# 3V3Regulator.net
KiCad netlist of a schematic drawn in Altium Designer
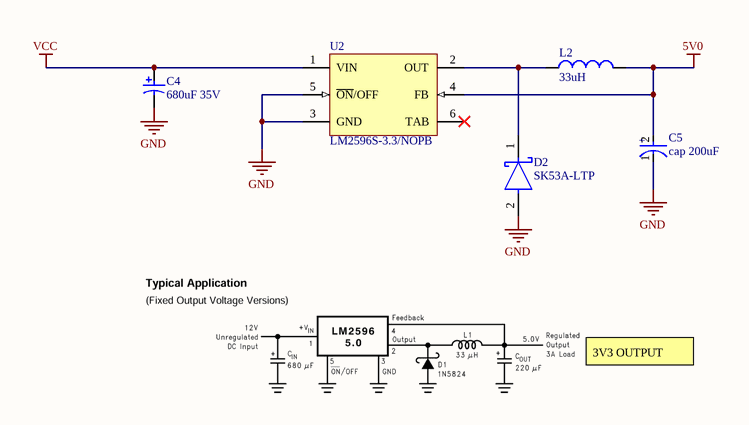
[diagram p0: 3V3Regulator.SchDoc]

(export (version "E")
  (design (tool "Eeschema 10.0.6"))
  (components
    (comp (ref "C4")
      (value "680uF 35V")
      (footprint "NIC-CAPA2-10X10_V")
      (fields (field (name "PARTNUMBER") "UUD1A681MNL1GS") (field (name "MANUFACTURER") "Nichicon"))
      (libsource (lib "Altium Content Vault") (part "NIC-CAP-P-2"))
    )
    (comp (ref "C5")
      (value "cap 200uF")
      (footprint "CAPAE7262X77M")
      (libsource (lib "Schlib1") (part "cap 200uF"))
    )
    (comp (ref "D2")
      (value "SK53A-LTP")
      (footprint "FP-DO-214AC-MFG")
      (description "DIODE SCHOTTKY 5A 30V SMA")
      (libsource (lib "Altium Content Vault") (part "1d6ec82d83fb6aee721767c19dac4b9"))
    )
    (comp (ref "L2")
      (value "33uH")
      (footprint "INDM140130X52N")
      (libsource (lib "Schlib1") (part "ind 330uH"))
    )
    (comp (ref "U2")
      (value "LM2596S-3.3/NOPB")
      (footprint "KTT0005B_M")
      (description "SIMPLE SWITCHER® Power Converter 150 KHz 3A Step-Down Voltage Regulator, 5-pin TO-263, Pb-Free")
      (fields (field (name "MANUFACTURER") "Texas Instruments"))
      (libsource (lib "Altium Content Vault") (part "PM-REG-LM2575HVS-12"))
    )
  )
  (nets
    (net (code "1") (name "5V0") (class "Default")
      (node (ref "C5") (pin "2") (pinfunction "A_2") (pintype "passive"))
      (node (ref "L2") (pin "2") (pinfunction "2_2") (pintype "passive"))
      (node (ref "U2") (pin "4") (pinfunction "FB_4") (pintype "input"))
    )
    (net (code "2") (name "GND") (class "Default")
      (node (ref "C4") (pin "2") (pinfunction "2_2") (pintype "passive"))
      (node (ref "C5") (pin "1") (pinfunction "C_1") (pintype "passive"))
      (node (ref "D2") (pin "2") (pinfunction "A_2") (pintype "passive"))
      (node (ref "U2") (pin "3") (pinfunction "GND_3") (pintype "power_in"))
      (node (ref "U2") (pin "5") (pinfunction "~{ON}/OFF_5") (pintype "input"))
    )
    (net (code "3") (name "Net-(D2-C)") (class "Default")
      (node (ref "D2") (pin "1") (pinfunction "C_1") (pintype "passive"))
      (node (ref "L2") (pin "1") (pinfunction "1_1") (pintype "passive"))
      (node (ref "U2") (pin "2") (pinfunction "OUT_2") (pintype "power_in"))
    )
    (net (code "4") (name "VCC") (class "Default")
      (node (ref "C4") (pin "1") (pinfunction "1_1") (pintype "passive"))
      (node (ref "U2") (pin "1") (pinfunction "VIN_1") (pintype "power_in"))
    )
    (net (code "5") (name "unconnected-(U2-TAB-Pad6)") (class "Default")
      (node (ref "U2") (pin "6") (pinfunction "TAB_6") (pintype "power_in+no_connect"))
    )
  )
)
